# Photodiode_plate.net
KiCad netlist of a schematic drawn in EasyEDA
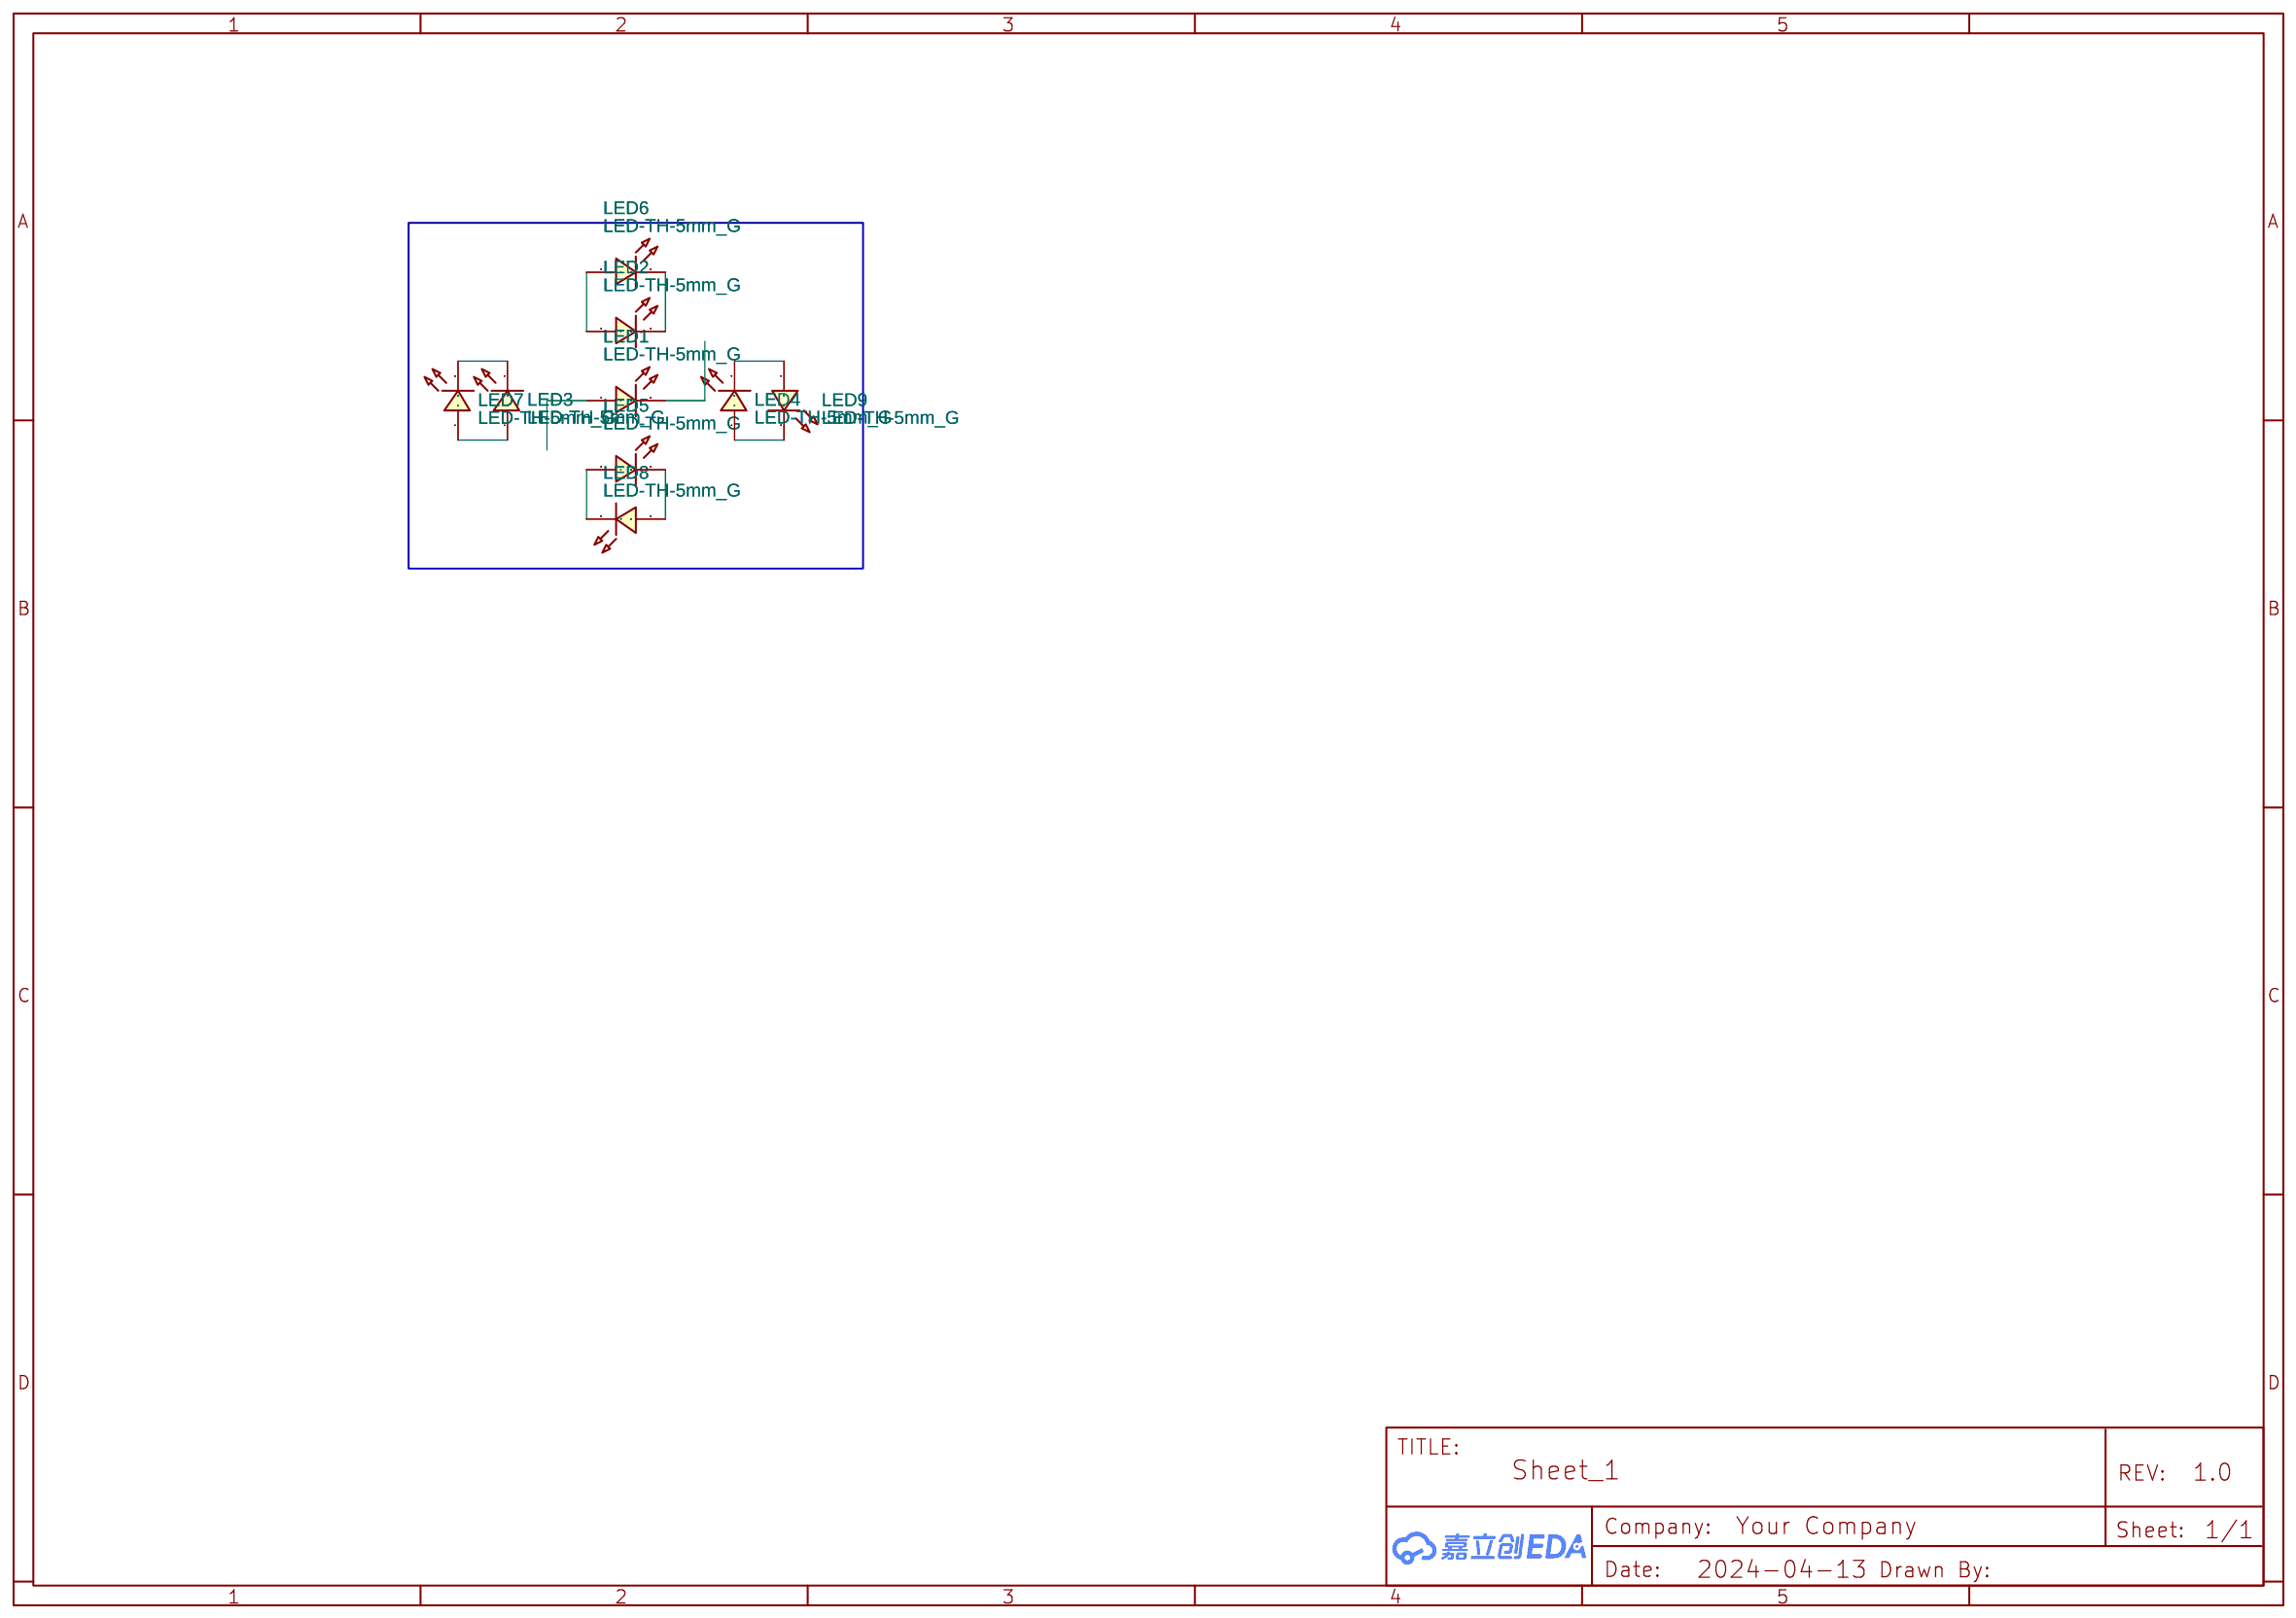
[diagram p0: schematic sheet]

(export (version "E")
  (design (tool "Eeschema 10.0.6"))
  (components
    (comp (ref "LED1")
      (value "LED-TH-5mm_G")
      (fields
        (field (name "BOM_Manufacturer Part") "333-2SYGD/S530-E2")
        (field (name "BOM_Supplier Part") "C88163")
      )
      (libsource (lib "") (part "LED-TH-5mm_G"))
    )
    (comp (ref "LED2")
      (value "LED-TH-5mm_G")
      (fields
        (field (name "BOM_Manufacturer Part") "333-2SYGD/S530-E2")
        (field (name "BOM_Supplier Part") "C88163")
      )
      (libsource (lib "") (part "LED-TH-5mm_G"))
    )
    (comp (ref "LED3")
      (value "LED-TH-5mm_G")
      (fields
        (field (name "BOM_Manufacturer Part") "333-2SYGD/S530-E2")
        (field (name "BOM_Supplier Part") "C88163")
      )
      (libsource (lib "") (part "LED-TH-5mm_G_2"))
    )
    (comp (ref "LED4")
      (value "LED-TH-5mm_G")
      (fields
        (field (name "BOM_Manufacturer Part") "333-2SYGD/S530-E2")
        (field (name "BOM_Supplier Part") "C88163")
      )
      (libsource (lib "") (part "LED-TH-5mm_G_2"))
    )
    (comp (ref "LED5")
      (value "LED-TH-5mm_G")
      (fields
        (field (name "BOM_Manufacturer Part") "333-2SYGD/S530-E2")
        (field (name "BOM_Supplier Part") "C88163")
      )
      (libsource (lib "") (part "LED-TH-5mm_G"))
    )
    (comp (ref "LED6")
      (value "LED-TH-5mm_G")
      (fields
        (field (name "BOM_Manufacturer Part") "333-2SYGD/S530-E2")
        (field (name "BOM_Supplier Part") "C88163")
      )
      (libsource (lib "") (part "LED-TH-5mm_G"))
    )
    (comp (ref "LED7")
      (value "LED-TH-5mm_G")
      (fields
        (field (name "BOM_Manufacturer Part") "333-2SYGD/S530-E2")
        (field (name "BOM_Supplier Part") "C88163")
      )
      (libsource (lib "") (part "LED-TH-5mm_G_2"))
    )
    (comp (ref "LED8")
      (value "LED-TH-5mm_G")
      (fields
        (field (name "BOM_Manufacturer Part") "333-2SYGD/S530-E2")
        (field (name "BOM_Supplier Part") "C88163")
      )
      (libsource (lib "") (part "LED-TH-5mm_G_3"))
    )
    (comp (ref "LED9")
      (value "LED-TH-5mm_G")
      (fields
        (field (name "BOM_Manufacturer Part") "333-2SYGD/S530-E2")
        (field (name "BOM_Supplier Part") "C88163")
      )
      (libsource (lib "") (part "LED-TH-5mm_G_1"))
    )
  )
  (nets
    (net (code "1") (name "Net-(LED2-Pad1)") (class "Default")
      (node (ref "LED2") (pin "1") (pinfunction "1_1") (pintype "unspecified"))
      (node (ref "LED6") (pin "1") (pinfunction "1_1") (pintype "unspecified"))
    )
    (net (code "2") (name "Net-(LED2-Pad2)") (class "Default")
      (node (ref "LED2") (pin "2") (pinfunction "2_2") (pintype "unspecified"))
      (node (ref "LED6") (pin "2") (pinfunction "2_2") (pintype "unspecified"))
    )
    (net (code "3") (name "Net-(LED3-Pad1)") (class "Default")
      (node (ref "LED3") (pin "1") (pinfunction "1_1") (pintype "unspecified"))
      (node (ref "LED7") (pin "1") (pinfunction "1_1") (pintype "unspecified"))
    )
    (net (code "4") (name "Net-(LED3-Pad2)") (class "Default")
      (node (ref "LED3") (pin "2") (pinfunction "2_2") (pintype "unspecified"))
      (node (ref "LED7") (pin "2") (pinfunction "2_2") (pintype "unspecified"))
    )
    (net (code "5") (name "Net-(LED4-Pad1)") (class "Default")
      (node (ref "LED4") (pin "1") (pinfunction "1_1") (pintype "unspecified"))
      (node (ref "LED9") (pin "2") (pinfunction "2_2") (pintype "unspecified"))
    )
    (net (code "6") (name "Net-(LED4-Pad2)") (class "Default")
      (node (ref "LED4") (pin "2") (pinfunction "2_2") (pintype "unspecified"))
      (node (ref "LED9") (pin "1") (pinfunction "1_1") (pintype "unspecified"))
    )
    (net (code "7") (name "Net-(LED5-Pad1)") (class "Default")
      (node (ref "LED5") (pin "1") (pinfunction "1_1") (pintype "unspecified"))
      (node (ref "LED8") (pin "2") (pinfunction "2_2") (pintype "unspecified"))
    )
    (net (code "8") (name "Net-(LED5-Pad2)") (class "Default")
      (node (ref "LED5") (pin "2") (pinfunction "2_2") (pintype "unspecified"))
      (node (ref "LED8") (pin "1") (pinfunction "1_1") (pintype "unspecified"))
    )
    (net (code "9") (name "unconnected-(LED1-Pad1)") (class "Default")
      (node (ref "LED1") (pin "1") (pinfunction "1_1") (pintype "unspecified"))
    )
    (net (code "10") (name "unconnected-(LED1-Pad2)") (class "Default")
      (node (ref "LED1") (pin "2") (pinfunction "2_2") (pintype "unspecified"))
    )
  )
)
